# FormulaControls.net
KiCad netlist of a schematic drawn in EAGLE
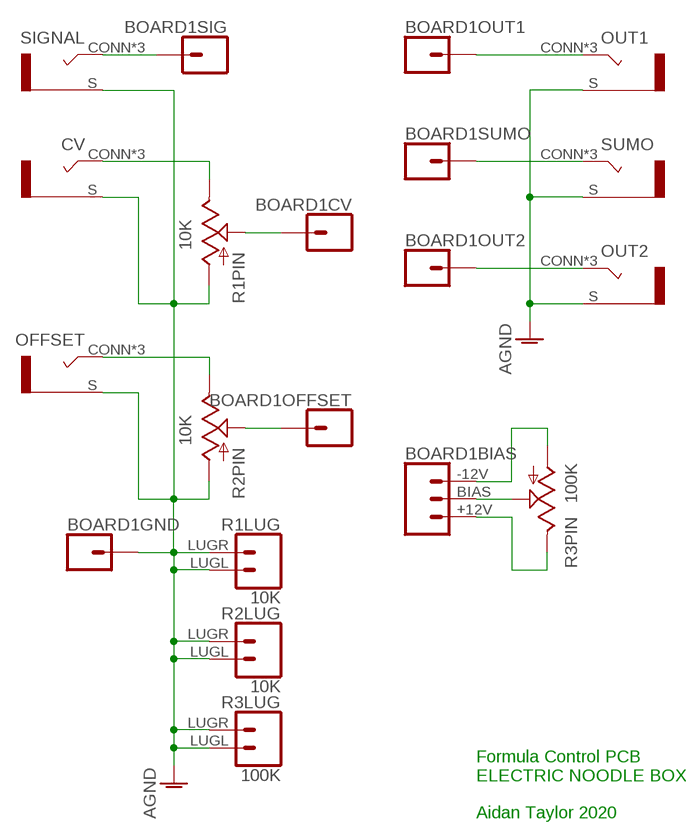
[diagram p0: schematic, sheet 1]

(export (version "E")
  (design (tool "Eeschema 10.0.6"))
  (components
    (comp (ref "BOARD1")
      (value "FORMULA_LINK")
      (footprint "eagle-import:FORMULA")
      (libsource (lib "eagle-import") (part "FORMULA_LINK"))
    )
    (comp (ref "CV")
      (value "COMBI-JACKCINCHNANA")
      (footprint "eagle-import:NEWCOMBOJACK_PANEL")
      (libsource (lib "eagle-import") (part "COMBI-JACKCINCHNANA"))
    )
    (comp (ref "OFFSET")
      (value "COMBI-JACKCINCHNANA")
      (footprint "eagle-import:NEWCOMBOJACK_PANEL")
      (libsource (lib "eagle-import") (part "COMBI-JACKCINCHNANA"))
    )
    (comp (ref "OUT1")
      (value "COMBI-JACKCINCHNANA")
      (footprint "eagle-import:NEWCOMBOJACK_PANEL")
      (libsource (lib "eagle-import") (part "COMBI-JACKCINCHNANA"))
    )
    (comp (ref "OUT2")
      (value "COMBI-JACKCINCHNANA")
      (footprint "eagle-import:NEWCOMBOJACK_PANEL")
      (libsource (lib "eagle-import") (part "COMBI-JACKCINCHNANA"))
    )
    (comp (ref "R1")
      (value "10K")
      (footprint "eagle-import:ALPHA_RV09_9MMPOT")
      (libsource (lib "eagle-import") (part "POTENTIOMETER"))
    )
    (comp (ref "R2")
      (value "10K")
      (footprint "eagle-import:ALPHA_RV09_9MMPOT")
      (libsource (lib "eagle-import") (part "POTENTIOMETER"))
    )
    (comp (ref "R3")
      (value "100K")
      (footprint "eagle-import:ALPHA_RV09_9MMPOT")
      (libsource (lib "eagle-import") (part "POTENTIOMETER"))
    )
    (comp (ref "SIGNAL")
      (value "COMBI-JACKCINCHNANA")
      (footprint "eagle-import:NEWCOMBOJACK_PANEL")
      (libsource (lib "eagle-import") (part "COMBI-JACKCINCHNANA"))
    )
    (comp (ref "SUMO")
      (value "COMBI-JACKCINCHNANA")
      (footprint "eagle-import:NEWCOMBOJACK_PANEL")
      (libsource (lib "eagle-import") (part "COMBI-JACKCINCHNANA"))
    )
  )
  (nets
    (net (code "1") (name "AGND") (class "Default")
      (node (ref "BOARD1") (pin "GND") (pinfunction "1_GND") (pintype "passive"))
      (node (ref "CV") (pin "S") (pinfunction "S_S") (pintype "passive"))
      (node (ref "OFFSET") (pin "S") (pinfunction "S_S") (pintype "passive"))
      (node (ref "OUT1") (pin "S") (pinfunction "S_S") (pintype "passive"))
      (node (ref "OUT2") (pin "S") (pinfunction "S_S") (pintype "passive"))
      (node (ref "R1") (pin "C1") (pinfunction "A_C1") (pintype "passive"))
      (node (ref "R1") (pin "LUGL") (pinfunction "1_LUGL") (pintype "passive"))
      (node (ref "R1") (pin "LUGR") (pinfunction "2_LUGR") (pintype "passive"))
      (node (ref "R2") (pin "C1") (pinfunction "A_C1") (pintype "passive"))
      (node (ref "R2") (pin "LUGL") (pinfunction "1_LUGL") (pintype "passive"))
      (node (ref "R2") (pin "LUGR") (pinfunction "2_LUGR") (pintype "passive"))
      (node (ref "R3") (pin "LUGL") (pinfunction "1_LUGL") (pintype "passive"))
      (node (ref "R3") (pin "LUGR") (pinfunction "2_LUGR") (pintype "passive"))
      (node (ref "SIGNAL") (pin "S") (pinfunction "S_S") (pintype "passive"))
      (node (ref "SUMO") (pin "S") (pinfunction "S_S") (pintype "passive"))
    )
    (net (code "2") (name "Net-(BOARD1A-1)") (class "Default")
      (node (ref "BOARD1") (pin "+12V") (pinfunction "1_+12V") (pintype "passive"))
      (node (ref "R3") (pin "C3") (pinfunction "B_C3") (pintype "passive"))
    )
    (net (code "3") (name "Net-(BOARD1A-2)") (class "Default")
      (node (ref "BOARD1") (pin "BIAS") (pinfunction "2_BIAS") (pintype "passive"))
      (node (ref "R3") (pin "C2") (pinfunction "W_C2") (pintype "passive"))
    )
    (net (code "4") (name "Net-(BOARD1A-3)") (class "Default")
      (node (ref "BOARD1") (pin "-12V") (pinfunction "3_-12V") (pintype "passive"))
      (node (ref "R3") (pin "C1") (pinfunction "A_C1") (pintype "passive"))
    )
    (net (code "5") (name "Net-(BOARD1B-1)") (class "Default")
      (node (ref "BOARD1") (pin "CV") (pinfunction "1_CV") (pintype "passive"))
      (node (ref "R1") (pin "C2") (pinfunction "W_C2") (pintype "passive"))
    )
    (net (code "6") (name "Net-(BOARD1D-1)") (class "Default")
      (node (ref "BOARD1") (pin "OFFSET") (pinfunction "1_OFFSET") (pintype "passive"))
      (node (ref "R2") (pin "C2") (pinfunction "W_C2") (pintype "passive"))
    )
    (net (code "7") (name "Net-(BOARD1E-1)") (class "Default")
      (node (ref "BOARD1") (pin "OUT1") (pinfunction "1_OUT1") (pintype "passive"))
      (node (ref "OUT1") (pin "CONN") (pinfunction "T_CONN") (pintype "passive"))
      (node (ref "OUT1") (pin "T1") (pinfunction "T_T1") (pintype "passive"))
      (node (ref "OUT1") (pin "T2") (pinfunction "T_T2") (pintype "passive"))
    )
    (net (code "8") (name "Net-(BOARD1F-1)") (class "Default")
      (node (ref "BOARD1") (pin "OUT2") (pinfunction "1_OUT2") (pintype "passive"))
      (node (ref "OUT2") (pin "CONN") (pinfunction "T_CONN") (pintype "passive"))
      (node (ref "OUT2") (pin "T1") (pinfunction "T_T1") (pintype "passive"))
      (node (ref "OUT2") (pin "T2") (pinfunction "T_T2") (pintype "passive"))
    )
    (net (code "9") (name "Net-(BOARD1G-1)") (class "Default")
      (node (ref "BOARD1") (pin "SIG") (pinfunction "1_SIG") (pintype "passive"))
      (node (ref "SIGNAL") (pin "CONN") (pinfunction "T_CONN") (pintype "passive"))
      (node (ref "SIGNAL") (pin "T1") (pinfunction "T_T1") (pintype "passive"))
      (node (ref "SIGNAL") (pin "T2") (pinfunction "T_T2") (pintype "passive"))
    )
    (net (code "10") (name "Net-(BOARD1H-1)") (class "Default")
      (node (ref "BOARD1") (pin "SUMO") (pinfunction "1_SUMO") (pintype "passive"))
      (node (ref "SUMO") (pin "CONN") (pinfunction "T_CONN") (pintype "passive"))
      (node (ref "SUMO") (pin "T1") (pinfunction "T_T1") (pintype "passive"))
      (node (ref "SUMO") (pin "T2") (pinfunction "T_T2") (pintype "passive"))
    )
    (net (code "11") (name "Net-(R1B-B)") (class "Default")
      (node (ref "CV") (pin "CONN") (pinfunction "T_CONN") (pintype "passive"))
      (node (ref "CV") (pin "T1") (pinfunction "T_T1") (pintype "passive"))
      (node (ref "CV") (pin "T2") (pinfunction "T_T2") (pintype "passive"))
      (node (ref "R1") (pin "C3") (pinfunction "B_C3") (pintype "passive"))
    )
    (net (code "12") (name "Net-(R2B-B)") (class "Default")
      (node (ref "OFFSET") (pin "CONN") (pinfunction "T_CONN") (pintype "passive"))
      (node (ref "OFFSET") (pin "T1") (pinfunction "T_T1") (pintype "passive"))
      (node (ref "OFFSET") (pin "T2") (pinfunction "T_T2") (pintype "passive"))
      (node (ref "R2") (pin "C3") (pinfunction "B_C3") (pintype "passive"))
    )
  )
)
